# USB.net
KiCad netlist of a schematic drawn in Altium Designer
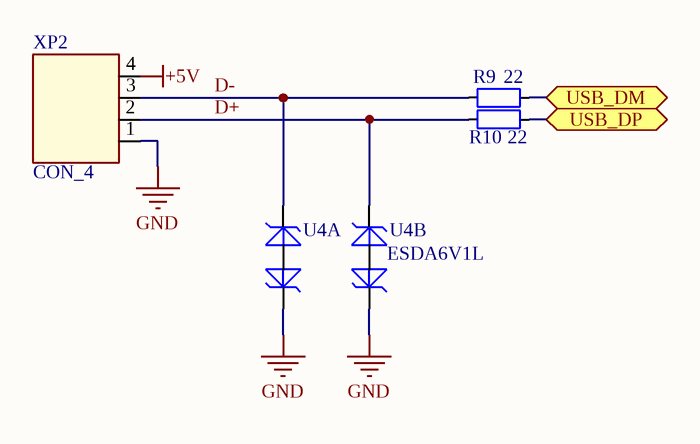
[diagram p0: USB.SchDoc]

(export (version "E")
  (design (tool "Eeschema 10.0.6"))
  (components
    (comp (ref "R9")
      (value "22")
      (footprint "DISCRETE:SMD_0603")
      (description "Resistor")
      (libsource (lib "DISCRETE") (part "RES"))
    )
    (comp (ref "R10")
      (value "22")
      (footprint "DISCRETE:SMD_0603")
      (description "Resistor")
      (libsource (lib "DISCRETE") (part "RES"))
    )
    (comp (ref "U4")
      (value "ESDA6V1L")
      (footprint "ICs:SOT23-3")
      (libsource (lib "ICs") (part "CDSOT23-SM712"))
    )
    (comp (ref "XP2")
      (value "CON_4")
      (footprint "Connectors:HEAD-SMD-2.54/4")
      (libsource (lib "Connectors") (part "CON_4"))
    )
  )
  (nets
    (net (code "1") (name "+5V") (class "Default")
      (node (ref "XP2") (pin "4") (pinfunction "4_4") (pintype "passive"))
    )
    (net (code "2") (name "/D+") (class "Default")
      (node (ref "R10") (pin "2") (pintype "passive"))
      (node (ref "U4") (pin "2") (pinfunction "2_2") (pintype "passive"))
      (node (ref "XP2") (pin "2") (pinfunction "2_2") (pintype "passive"))
    )
    (net (code "3") (name "/D-") (class "Default")
      (node (ref "R9") (pin "2") (pintype "passive"))
      (node (ref "U4") (pin "1") (pinfunction "1_1") (pintype "passive"))
      (node (ref "XP2") (pin "3") (pinfunction "3_3") (pintype "passive"))
    )
    (net (code "4") (name "/USB_DM") (class "Default") (node (ref "R9") (pin "1") (pintype "passive")))
    (net (code "5") (name "/USB_DP") (class "Default") (node (ref "R10") (pin "1") (pintype "passive")))
    (net (code "6") (name "GND") (class "Default")
      (node (ref "U4") (pin "3") (pinfunction "3_3") (pintype "passive"))
      (node (ref "XP2") (pin "1") (pinfunction "1_1") (pintype "passive"))
    )
  )
)
